# Adafruit_Voice_Bonnet.net
KiCad netlist of a schematic drawn in EAGLE
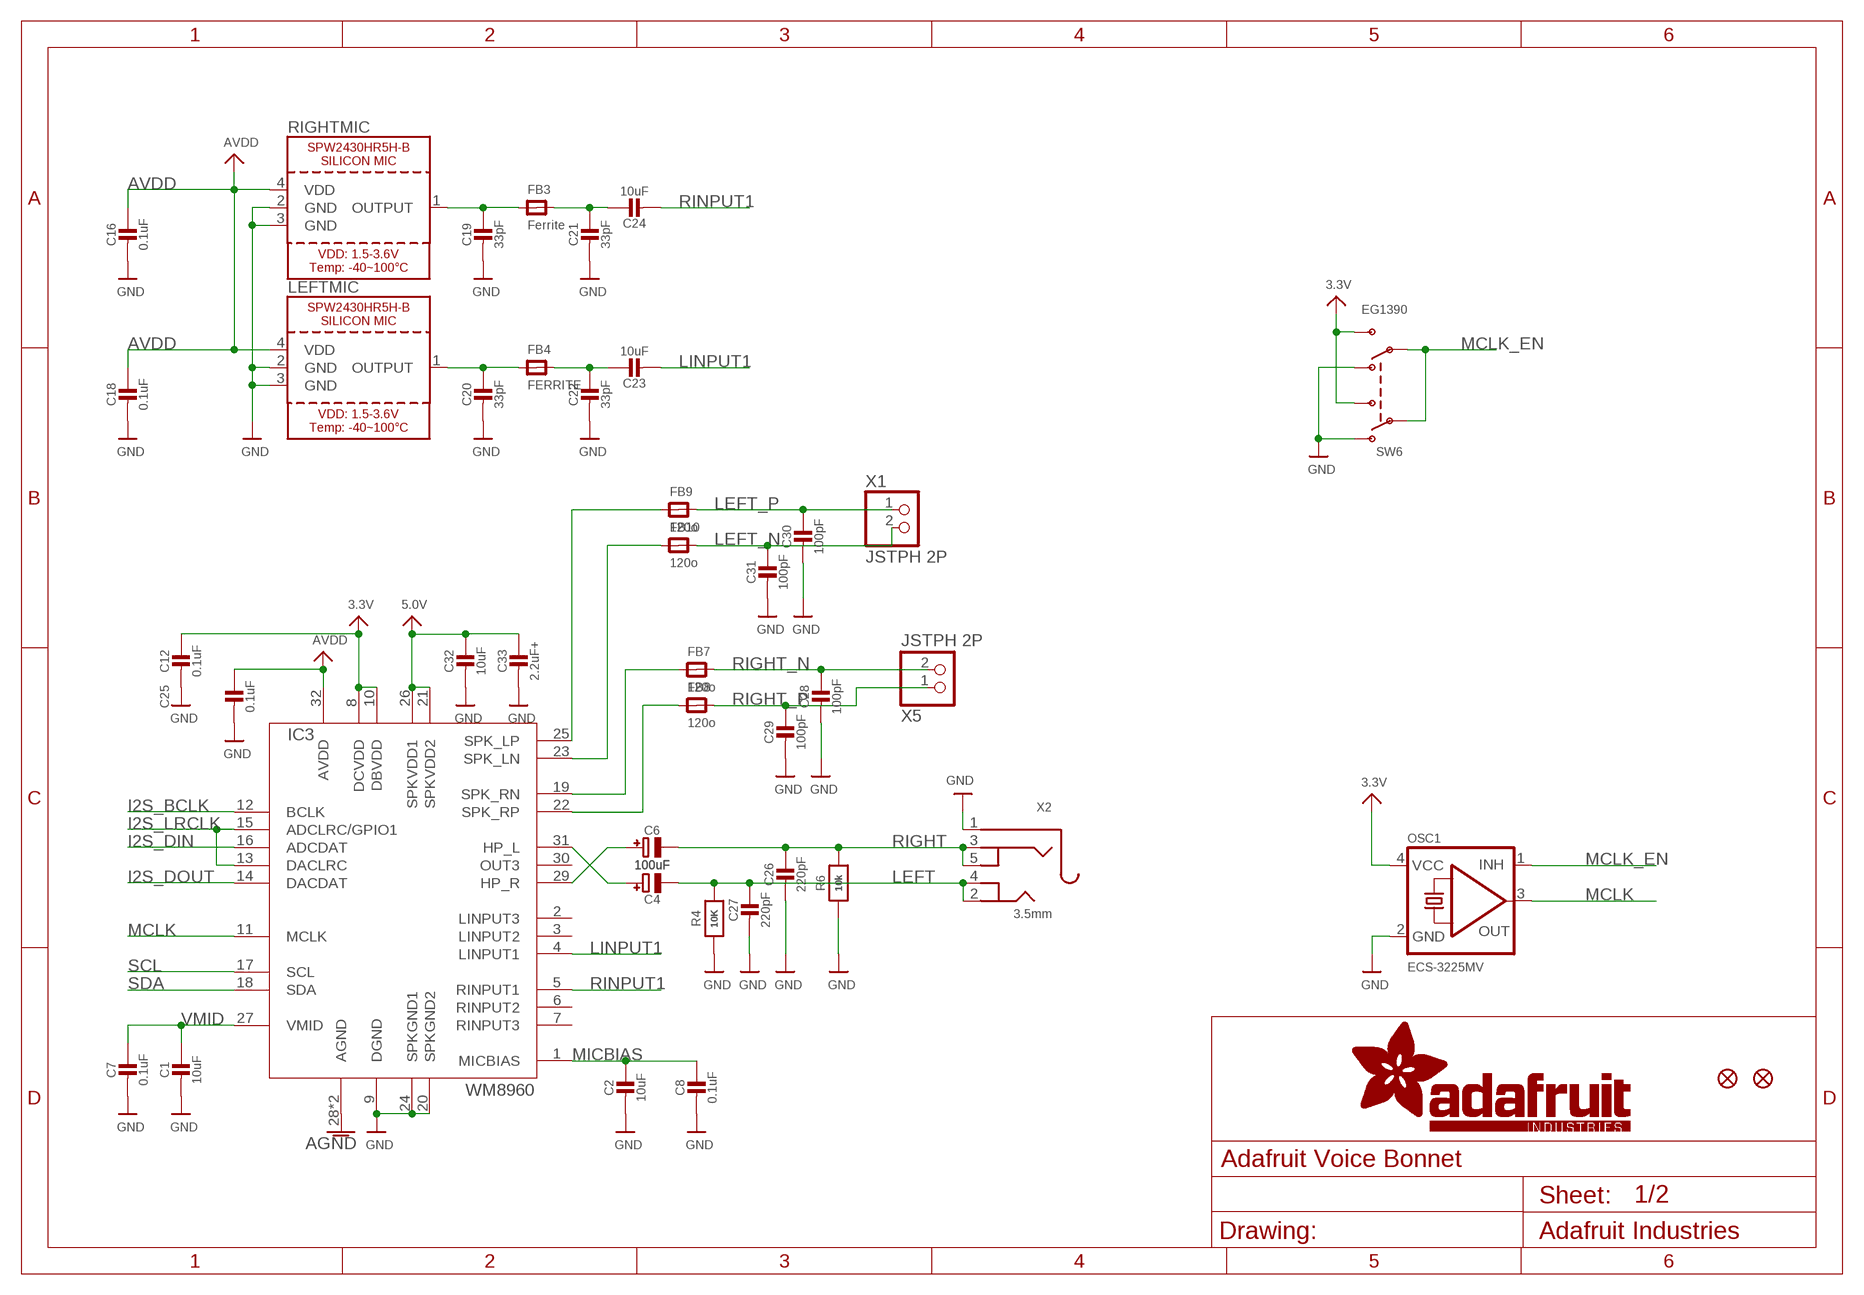
[diagram p0: schematic, sheet 1]
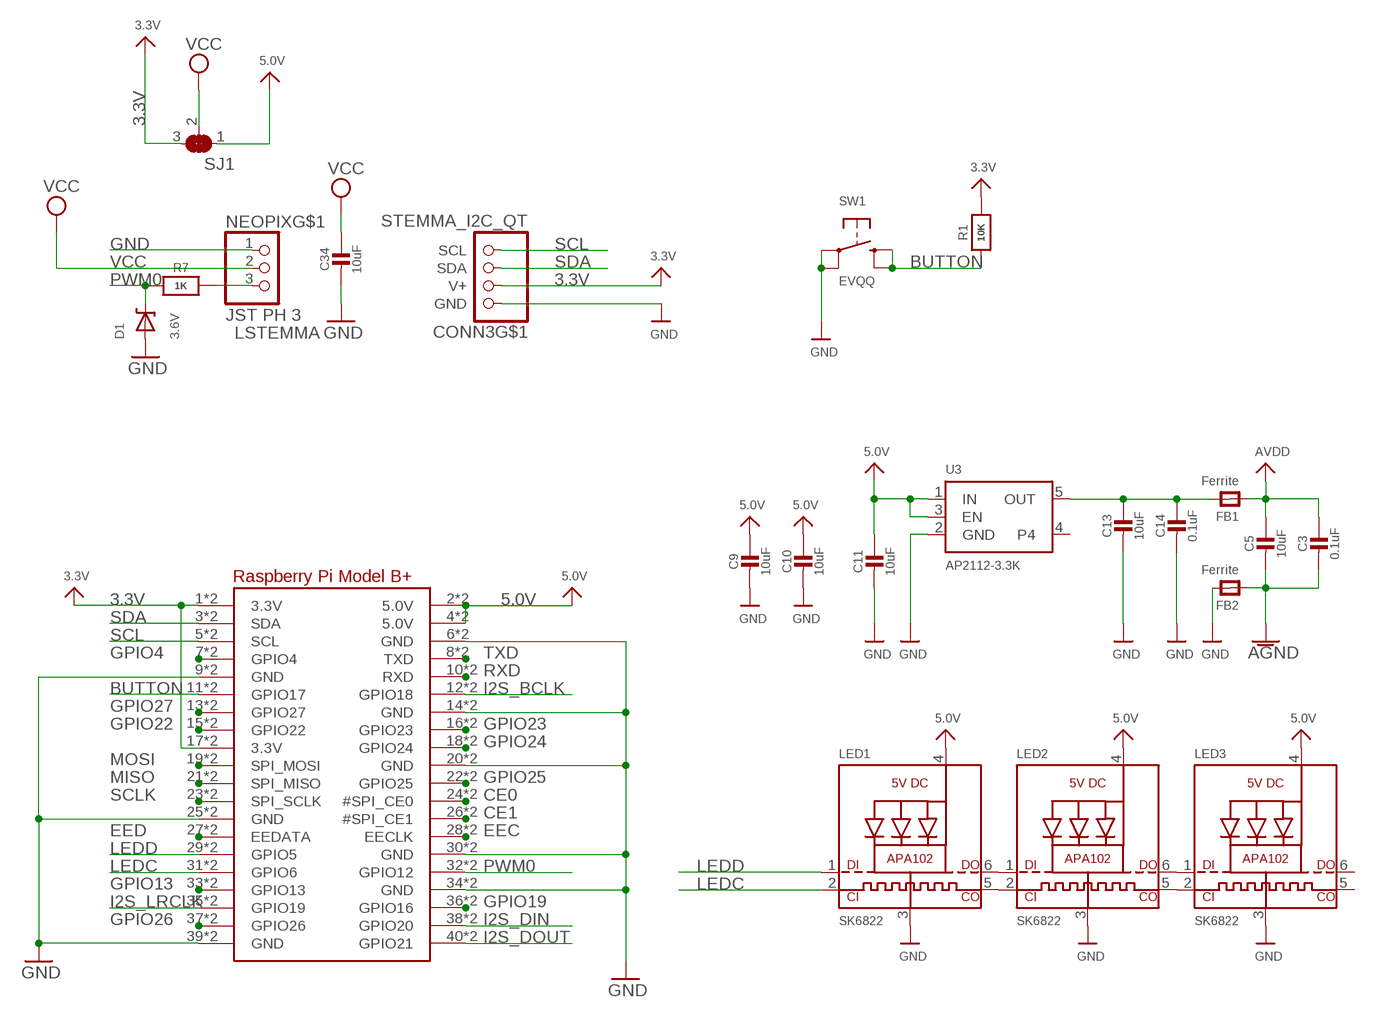
[diagram p1: schematic, sheet 2]

(export (version "E")
  (design (tool "Eeschema 10.0.6"))
  (components
    (comp (ref "C1")
      (value "10uF")
      (footprint "eagle-import:0805-NO")
      (libsource (lib "eagle-import") (part "CAP_CERAMIC0805-NOOUTLINE"))
    )
    (comp (ref "C2")
      (value "10uF")
      (footprint "eagle-import:0805-NO")
      (libsource (lib "eagle-import") (part "CAP_CERAMIC0805-NOOUTLINE"))
    )
    (comp (ref "C4")
      (value "100uF")
      (footprint "eagle-import:PANASONIC_C")
      (libsource (lib "eagle-import") (part "CAP_ELECTROLYTICPANASONIC_C"))
    )
    (comp (ref "C6")
      (value "100uF")
      (footprint "eagle-import:PANASONIC_C")
      (libsource (lib "eagle-import") (part "CAP_ELECTROLYTICPANASONIC_C"))
    )
    (comp (ref "C7")
      (value "0.1uF")
      (footprint "eagle-import:0603-NO")
      (libsource (lib "eagle-import") (part "CAP_CERAMIC0603_NO"))
    )
    (comp (ref "C8")
      (value "0.1uF")
      (footprint "eagle-import:0603-NO")
      (libsource (lib "eagle-import") (part "CAP_CERAMIC0603_NO"))
    )
    (comp (ref "C12")
      (value "0.1uF")
      (footprint "eagle-import:0603-NO")
      (libsource (lib "eagle-import") (part "CAP_CERAMIC0603_NO"))
    )
    (comp (ref "C16")
      (value "0.1uF")
      (footprint "eagle-import:0603-NO")
      (libsource (lib "eagle-import") (part "CAP_CERAMIC0603_NO"))
    )
    (comp (ref "C18")
      (value "0.1uF")
      (footprint "eagle-import:0603-NO")
      (libsource (lib "eagle-import") (part "CAP_CERAMIC0603_NO"))
    )
    (comp (ref "C19")
      (value "33pF")
      (footprint "eagle-import:0603-NO")
      (libsource (lib "eagle-import") (part "CAP_CERAMIC0603_NO"))
    )
    (comp (ref "C20")
      (value "33pF")
      (footprint "eagle-import:0603-NO")
      (libsource (lib "eagle-import") (part "CAP_CERAMIC0603_NO"))
    )
    (comp (ref "C21")
      (value "33pF")
      (footprint "eagle-import:0603-NO")
      (libsource (lib "eagle-import") (part "CAP_CERAMIC0603_NO"))
    )
    (comp (ref "C22")
      (value "33pF")
      (footprint "eagle-import:0603-NO")
      (libsource (lib "eagle-import") (part "CAP_CERAMIC0603_NO"))
    )
    (comp (ref "C23")
      (value "10uF")
      (footprint "eagle-import:0805-NO")
      (libsource (lib "eagle-import") (part "CAP_CERAMIC0805-NOOUTLINE"))
    )
    (comp (ref "C24")
      (value "10uF")
      (footprint "eagle-import:0805-NO")
      (libsource (lib "eagle-import") (part "CAP_CERAMIC0805-NOOUTLINE"))
    )
    (comp (ref "C25")
      (value "0.1uF")
      (footprint "eagle-import:0603-NO")
      (libsource (lib "eagle-import") (part "CAP_CERAMIC0603_NO"))
    )
    (comp (ref "C26")
      (value "220pF")
      (footprint "eagle-import:0603-NO")
      (libsource (lib "eagle-import") (part "CAP_CERAMIC0603_NO"))
    )
    (comp (ref "C27")
      (value "220pF")
      (footprint "eagle-import:0603-NO")
      (libsource (lib "eagle-import") (part "CAP_CERAMIC0603_NO"))
    )
    (comp (ref "C28")
      (value "100pF")
      (footprint "eagle-import:0603-NO")
      (libsource (lib "eagle-import") (part "CAP_CERAMIC0603_NO"))
    )
    (comp (ref "C29")
      (value "100pF")
      (footprint "eagle-import:0603-NO")
      (libsource (lib "eagle-import") (part "CAP_CERAMIC0603_NO"))
    )
    (comp (ref "C30")
      (value "100pF")
      (footprint "eagle-import:0603-NO")
      (libsource (lib "eagle-import") (part "CAP_CERAMIC0603_NO"))
    )
    (comp (ref "C31")
      (value "100pF")
      (footprint "eagle-import:0603-NO")
      (libsource (lib "eagle-import") (part "CAP_CERAMIC0603_NO"))
    )
    (comp (ref "C32")
      (value "10uF")
      (footprint "eagle-import:0805-NO")
      (libsource (lib "eagle-import") (part "CAP_CERAMIC0805-NOOUTLINE"))
    )
    (comp (ref "C33")
      (value "2.2uF+")
      (footprint "eagle-import:0805-NO")
      (libsource (lib "eagle-import") (part "CAP_CERAMIC0805-NOOUTLINE"))
    )
    (comp (ref "FB3")
      (value "Ferrite")
      (footprint "eagle-import:0805-NO")
      (libsource (lib "eagle-import") (part "FERRITE-0805NO"))
    )
    (comp (ref "FB4")
      (value "FERRITE")
      (footprint "eagle-import:0805-NO")
      (libsource (lib "eagle-import") (part "FERRITE-0805NO"))
    )
    (comp (ref "FB7")
      (value "120o")
      (footprint "eagle-import:0805-NO")
      (libsource (lib "eagle-import") (part "FERRITE-0805NO"))
    )
    (comp (ref "FB8")
      (value "120o")
      (footprint "eagle-import:0805-NO")
      (libsource (lib "eagle-import") (part "FERRITE-0805NO"))
    )
    (comp (ref "FB9")
      (value "120o")
      (footprint "eagle-import:0805-NO")
      (libsource (lib "eagle-import") (part "FERRITE-0805NO"))
    )
    (comp (ref "FB10")
      (value "120o")
      (footprint "eagle-import:0805-NO")
      (libsource (lib "eagle-import") (part "FERRITE-0805NO"))
    )
    (comp (ref "FID1")
      (value "FIDUCIAL_1MM")
      (footprint "eagle-import:FIDUCIAL_1MM")
      (libsource (lib "eagle-import") (part "FIDUCIAL_1MM"))
    )
    (comp (ref "FID2")
      (value "FIDUCIAL_1MM")
      (footprint "eagle-import:FIDUCIAL_1MM")
      (libsource (lib "eagle-import") (part "FIDUCIAL_1MM"))
    )
    (comp (ref "IC3")
      (value "WM8960")
      (footprint "eagle-import:QFN32_5MM")
      (libsource (lib "eagle-import") (part "WM8960"))
    )
    (comp (ref "LEFTMIC")
      (value "SPW2430HR5H-B")
      (footprint "eagle-import:SPW2430HR5H-B")
      (libsource (lib "eagle-import") (part "SPW2430HR5H-B"))
    )
    (comp (ref "OSC1")
      (value "ECS-3225MV")
      (footprint "eagle-import:OSC_3.2X2.5MM")
      (libsource (lib "eagle-import") (part "OSCILLATOR3.2X2.5"))
    )
    (comp (ref "R4")
      (value "10K")
      (footprint "eagle-import:0603-NO")
      (libsource (lib "eagle-import") (part "RESISTOR_0603_NOOUT"))
    )
    (comp (ref "R6")
      (value "10k")
      (footprint "eagle-import:0603-NO")
      (libsource (lib "eagle-import") (part "RESISTOR_0603_NOOUT"))
    )
    (comp (ref "RIGHTMIC")
      (value "SPW2430HR5H-B")
      (footprint "eagle-import:SPW2430HR5H-B")
      (libsource (lib "eagle-import") (part "SPW2430HR5H-B"))
    )
    (comp (ref "SW6")
      (value "EG1390")
      (footprint "eagle-import:EG1390")
      (libsource (lib "eagle-import") (part "SWITCH_DPDTEG1390"))
    )
    (comp (ref "X1")
      (value "JSTPH 2P")
      (footprint "eagle-import:JSTPH2")
      (libsource (lib "eagle-import") (part "CON_JST_PH_2PIN"))
    )
    (comp (ref "X2")
      (value "3.5mm")
      (footprint "eagle-import:4UCONN_19269")
      (libsource (lib "eagle-import") (part "AUDIO_3.5MMJACK"))
    )
    (comp (ref "X5")
      (value "JSTPH 2P")
      (footprint "eagle-import:JSTPH2")
      (libsource (lib "eagle-import") (part "CON_JST_PH_2PIN"))
    )
    (comp (ref "C3")
      (value "0.1uF")
      (footprint "eagle-import:0603-NO")
      (libsource (lib "eagle-import") (part "CAP_CERAMIC0603_NO"))
    )
    (comp (ref "C5")
      (value "10uF")
      (footprint "eagle-import:0805-NO")
      (libsource (lib "eagle-import") (part "CAP_CERAMIC0805-NOOUTLINE"))
    )
    (comp (ref "C9")
      (value "10uF")
      (footprint "eagle-import:0805-NO")
      (libsource (lib "eagle-import") (part "CAP_CERAMIC0805-NOOUTLINE"))
    )
    (comp (ref "C10")
      (value "10uF")
      (footprint "eagle-import:0805-NO")
      (libsource (lib "eagle-import") (part "CAP_CERAMIC0805-NOOUTLINE"))
    )
    (comp (ref "C11")
      (value "10uF")
      (footprint "eagle-import:0805-NO")
      (libsource (lib "eagle-import") (part "CAP_CERAMIC0805-NOOUTLINE"))
    )
    (comp (ref "C13")
      (value "10uF")
      (footprint "eagle-import:0805-NO")
      (libsource (lib "eagle-import") (part "CAP_CERAMIC0805-NOOUTLINE"))
    )
    (comp (ref "C14")
      (value "0.1uF")
      (footprint "eagle-import:0603-NO")
      (libsource (lib "eagle-import") (part "CAP_CERAMIC0603_NO"))
    )
    (comp (ref "C34")
      (value "10uF")
      (footprint "eagle-import:0805-NO")
      (libsource (lib "eagle-import") (part "CAP_CERAMIC0805-NOOUTLINE"))
    )
    (comp (ref "CONN3")
      (value "STEMMA_I2C_QT")
      (footprint "eagle-import:JST_SH4")
      (libsource (lib "eagle-import") (part "STEMMA_I2C_QT"))
    )
    (comp (ref "D1")
      (value "3.6V")
      (footprint "eagle-import:SOD-323")
      (libsource (lib "eagle-import") (part "DIODE-ZENERSOD323"))
    )
    (comp (ref "FB1")
      (value "Ferrite")
      (footprint "eagle-import:0805")
      (libsource (lib "eagle-import") (part "FERRITE0805"))
    )
    (comp (ref "FB2")
      (value "Ferrite")
      (footprint "eagle-import:0805")
      (libsource (lib "eagle-import") (part "FERRITE0805"))
    )
    (comp (ref "LED1")
      (value "SK6822")
      (footprint "eagle-import:APA102")
      (libsource (lib "eagle-import") (part "APA102"))
    )
    (comp (ref "LED2")
      (value "SK6822")
      (footprint "eagle-import:APA102")
      (libsource (lib "eagle-import") (part "APA102"))
    )
    (comp (ref "LED3")
      (value "SK6822")
      (footprint "eagle-import:APA102")
      (libsource (lib "eagle-import") (part "APA102"))
    )
    (comp (ref "NEOPIX")
      (value "JST PH 3")
      (footprint "eagle-import:JSTPH3")
      (libsource (lib "eagle-import") (part "CON_JST_PH_3PIN"))
    )
    (comp (ref "R1")
      (value "10K")
      (footprint "eagle-import:0603-NO")
      (libsource (lib "eagle-import") (part "RESISTOR_0603_NOOUT"))
    )
    (comp (ref "R7")
      (value "1K")
      (footprint "eagle-import:0603-NO")
      (libsource (lib "eagle-import") (part "RESISTOR_0603_NOOUT"))
    )
    (comp (ref "RPI1")
      (value "RASPBERRYPI_BPLUS_BONNET_THMSMT")
      (footprint "eagle-import:PI_BONNET_THMSMT")
      (libsource (lib "eagle-import") (part "RASPBERRYPI_BPLUS_BONNET_THMSMT"))
    )
    (comp (ref "SJ1")
      (value "SOLDERJUMPER_2WAY")
      (footprint "eagle-import:SOLDERJUMPER_2WAY_OPEN_NOPASTE")
      (libsource (lib "eagle-import") (part "SOLDERJUMPER_2WAY"))
    )
    (comp (ref "SW1")
      (value "EVQQ")
      (footprint "eagle-import:EVQ-Q2_SMALLER")
      (libsource (lib "eagle-import") (part "SWITCH_TACT_SMT_EVQQ2_SMALL"))
    )
    (comp (ref "U3")
      (value "AP2112-3.3K")
      (footprint "eagle-import:SOT23-5")
      (libsource (lib "eagle-import") (part "VREG_SOT23-5"))
    )
  )
  (nets
    (net (code "1") (name "3.3V") (class "Default")
      (node (ref "C12") (pin "1") (pinfunction "1_1") (pintype "passive"))
      (node (ref "CONN3") (pin "2") (pinfunction "V+_2") (pintype "passive"))
      (node (ref "IC3") (pin "10") (pinfunction "DBVDD_10") (pintype "power_in"))
      (node (ref "IC3") (pin "8") (pinfunction "DCVDD_8") (pintype "power_in"))
      (node (ref "OSC1") (pin "4") (pinfunction "VCC_4") (pintype "power_in"))
      (node (ref "R1") (pin "2") (pinfunction "2_2") (pintype "passive"))
      (node (ref "RPI1") (pin "1") (pinfunction "3.3V_1") (pintype "power_in"))
      (node (ref "RPI1") (pin "17") (pinfunction "3.3V_17") (pintype "power_in"))
      (node (ref "RPI1") (pin "S1") (pinfunction "3.3V_S1") (pintype "power_in"))
      (node (ref "RPI1") (pin "S17") (pinfunction "3.3V_S17") (pintype "power_in"))
      (node (ref "SJ1") (pin "3") (pinfunction "3_3") (pintype "passive"))
      (node (ref "SW6") (pin "S1") (pinfunction "S1_S1") (pintype "passive"))
      (node (ref "SW6") (pin "S2") (pinfunction "S2_S2") (pintype "passive"))
    )
    (net (code "2") (name "5.0V") (class "Default")
      (node (ref "C10") (pin "1") (pinfunction "1_1") (pintype "passive"))
      (node (ref "C11") (pin "1") (pinfunction "1_1") (pintype "passive"))
      (node (ref "C32") (pin "1") (pinfunction "1_1") (pintype "passive"))
      (node (ref "C33") (pin "1") (pinfunction "1_1") (pintype "passive"))
      (node (ref "C9") (pin "1") (pinfunction "1_1") (pintype "passive"))
      (node (ref "IC3") (pin "21") (pinfunction "SPKVDD2_21") (pintype "power_in"))
      (node (ref "IC3") (pin "26") (pinfunction "SPKVDD1_26") (pintype "power_in"))
      (node (ref "LED1") (pin "4") (pinfunction "VDD_4") (pintype "power_in"))
      (node (ref "LED2") (pin "4") (pinfunction "VDD_4") (pintype "power_in"))
      (node (ref "LED3") (pin "4") (pinfunction "VDD_4") (pintype "power_in"))
      (node (ref "RPI1") (pin "2") (pinfunction "5.0V_2") (pintype "power_in"))
      (node (ref "RPI1") (pin "4") (pinfunction "5.0V_4") (pintype "power_in"))
      (node (ref "RPI1") (pin "S2") (pinfunction "5.0V_S2") (pintype "power_in"))
      (node (ref "RPI1") (pin "S4") (pinfunction "5.0V_S4") (pintype "power_in"))
      (node (ref "SJ1") (pin "1") (pinfunction "1_1") (pintype "passive"))
      (node (ref "U3") (pin "1") (pinfunction "IN_1") (pintype "power_in"))
      (node (ref "U3") (pin "3") (pinfunction "EN_3") (pintype "input"))
    )
    (net (code "3") (name "AGND") (class "Default")
      (node (ref "C3") (pin "2") (pinfunction "2_2") (pintype "passive"))
      (node (ref "C5") (pin "2") (pinfunction "2_2") (pintype "passive"))
      (node (ref "FB2") (pin "1") (pinfunction "P$1_1") (pintype "passive"))
      (node (ref "IC3") (pin "28") (pinfunction "AGND_28") (pintype "power_in"))
      (node (ref "IC3") (pin "33") (pinfunction "AGND_33") (pintype "power_in"))
    )
    (net (code "4") (name "AVDD") (class "Default")
      (node (ref "C16") (pin "1") (pinfunction "1_1") (pintype "passive"))
      (node (ref "C18") (pin "1") (pinfunction "1_1") (pintype "passive"))
      (node (ref "C25") (pin "1") (pinfunction "1_1") (pintype "passive"))
      (node (ref "C3") (pin "1") (pinfunction "1_1") (pintype "passive"))
      (node (ref "C5") (pin "1") (pinfunction "1_1") (pintype "passive"))
      (node (ref "FB1") (pin "1") (pinfunction "P$1_1") (pintype "passive"))
      (node (ref "IC3") (pin "32") (pinfunction "AVDD_32") (pintype "power_in"))
      (node (ref "LEFTMIC") (pin "4") (pinfunction "VDD_4") (pintype "power_in"))
      (node (ref "RIGHTMIC") (pin "4") (pinfunction "VDD_4") (pintype "power_in"))
    )
    (net (code "5") (name "BUTTON") (class "Default")
      (node (ref "R1") (pin "1") (pinfunction "1_1") (pintype "passive"))
      (node (ref "RPI1") (pin "11") (pinfunction "GPIO17_11") (pintype "bidirectional"))
      (node (ref "RPI1") (pin "S11") (pinfunction "GPIO17_S11") (pintype "bidirectional"))
      (node (ref "SW1") (pin "B") (pinfunction "S_B") (pintype "passive"))
      (node (ref "SW1") (pin "B'") (pinfunction "S1_B'") (pintype "passive"))
    )
    (net (code "10") (name "CE0") (class "Default")
      (node (ref "RPI1") (pin "24") (pinfunction "#SPI_CE0_24") (pintype "bidirectional"))
      (node (ref "RPI1") (pin "S24") (pinfunction "#SPI_CE0_S24") (pintype "bidirectional"))
    )
    (net (code "20") (name "CE1") (class "Default")
      (node (ref "RPI1") (pin "26") (pinfunction "#SPI_CE1_26") (pintype "bidirectional"))
      (node (ref "RPI1") (pin "S26") (pinfunction "#SPI_CE1_S26") (pintype "bidirectional"))
    )
    (net (code "21") (name "EEC") (class "Default")
      (node (ref "RPI1") (pin "28") (pinfunction "EECLK_28") (pintype "bidirectional"))
      (node (ref "RPI1") (pin "S28") (pinfunction "EECLK_S28") (pintype "bidirectional"))
    )
    (net (code "22") (name "EED") (class "Default")
      (node (ref "RPI1") (pin "27") (pinfunction "EEDATA_27") (pintype "bidirectional"))
      (node (ref "RPI1") (pin "S27") (pinfunction "EEDATA_S27") (pintype "bidirectional"))
    )
    (net (code "23") (name "GND") (class "Default")
      (node (ref "C1") (pin "2") (pinfunction "2_2") (pintype "passive"))
      (node (ref "C10") (pin "2") (pinfunction "2_2") (pintype "passive"))
      (node (ref "C11") (pin "2") (pinfunction "2_2") (pintype "passive"))
      (node (ref "C12") (pin "2") (pinfunction "2_2") (pintype "passive"))
      (node (ref "C13") (pin "2") (pinfunction "2_2") (pintype "passive"))
      (node (ref "C14") (pin "2") (pinfunction "2_2") (pintype "passive"))
      (node (ref "C16") (pin "2") (pinfunction "2_2") (pintype "passive"))
      (node (ref "C18") (pin "2") (pinfunction "2_2") (pintype "passive"))
      (node (ref "C19") (pin "2") (pinfunction "2_2") (pintype "passive"))
      (node (ref "C2") (pin "2") (pinfunction "2_2") (pintype "passive"))
      (node (ref "C20") (pin "2") (pinfunction "2_2") (pintype "passive"))
      (node (ref "C21") (pin "2") (pinfunction "2_2") (pintype "passive"))
      (node (ref "C22") (pin "2") (pinfunction "2_2") (pintype "passive"))
      (node (ref "C25") (pin "2") (pinfunction "2_2") (pintype "passive"))
      (node (ref "C26") (pin "2") (pinfunction "2_2") (pintype "passive"))
      (node (ref "C27") (pin "2") (pinfunction "2_2") (pintype "passive"))
      (node (ref "C28") (pin "2") (pinfunction "2_2") (pintype "passive"))
      (node (ref "C29") (pin "2") (pinfunction "2_2") (pintype "passive"))
      (node (ref "C30") (pin "2") (pinfunction "2_2") (pintype "passive"))
      (node (ref "C31") (pin "2") (pinfunction "2_2") (pintype "passive"))
      (node (ref "C32") (pin "2") (pinfunction "2_2") (pintype "passive"))
      (node (ref "C33") (pin "2") (pinfunction "2_2") (pintype "passive"))
      (node (ref "C34") (pin "2") (pinfunction "2_2") (pintype "passive"))
      (node (ref "C7") (pin "2") (pinfunction "2_2") (pintype "passive"))
      (node (ref "C8") (pin "2") (pinfunction "2_2") (pintype "passive"))
      (node (ref "C9") (pin "2") (pinfunction "2_2") (pintype "passive"))
      (node (ref "CONN3") (pin "1") (pinfunction "GND_1") (pintype "passive"))
      (node (ref "D1") (pin "A") (pinfunction "A_A") (pintype "passive"))
      (node (ref "FB2") (pin "2") (pinfunction "P$2_2") (pintype "passive"))
      (node (ref "IC3") (pin "20") (pinfunction "SPKGND2_20") (pintype "power_in"))
      (node (ref "IC3") (pin "24") (pinfunction "SPKGND1_24") (pintype "power_in"))
      (node (ref "IC3") (pin "9") (pinfunction "DGND_9") (pintype "power_in"))
      (node (ref "LED1") (pin "3") (pinfunction "GND_3") (pintype "power_in"))
      (node (ref "LED2") (pin "3") (pinfunction "GND_3") (pintype "power_in"))
      (node (ref "LED3") (pin "3") (pinfunction "GND_3") (pintype "power_in"))
      (node (ref "LEFTMIC") (pin "2") (pinfunction "GND_2") (pintype "power_in"))
      (node (ref "LEFTMIC") (pin "3") (pinfunction "GND_3") (pintype "power_in"))
      (node (ref "NEOPIX") (pin "1") (pinfunction "1_1") (pintype "passive"))
      (node (ref "OSC1") (pin "2") (pinfunction "GND_2") (pintype "power_in"))
      (node (ref "R4") (pin "1") (pinfunction "1_1") (pintype "passive"))
      (node (ref "R6") (pin "1") (pinfunction "1_1") (pintype "passive"))
      (node (ref "RIGHTMIC") (pin "2") (pinfunction "GND_2") (pintype "power_in"))
      (node (ref "RIGHTMIC") (pin "3") (pinfunction "GND_3") (pintype "power_in"))
      (node (ref "RPI1") (pin "14") (pinfunction "GND_14") (pintype "power_in"))
      (node (ref "RPI1") (pin "20") (pinfunction "GND_20") (pintype "power_in"))
      (node (ref "RPI1") (pin "25") (pinfunction "GND_25") (pintype "power_in"))
      (node (ref "RPI1") (pin "30") (pinfunction "GND_30") (pintype "power_in"))
      (node (ref "RPI1") (pin "34") (pinfunction "GND_34") (pintype "power_in"))
      (node (ref "RPI1") (pin "39") (pinfunction "GND_39") (pintype "power_in"))
      (node (ref "RPI1") (pin "6") (pinfunction "GND_6") (pintype "power_in"))
      (node (ref "RPI1") (pin "9") (pinfunction "GND_9") (pintype "power_in"))
      (node (ref "RPI1") (pin "S14") (pinfunction "GND_S14") (pintype "power_in"))
      (node (ref "RPI1") (pin "S20") (pinfunction "GND_S20") (pintype "power_in"))
      (node (ref "RPI1") (pin "S25") (pinfunction "GND_S25") (pintype "power_in"))
      (node (ref "RPI1") (pin "S30") (pinfunction "GND_S30") (pintype "power_in"))
      (node (ref "RPI1") (pin "S34") (pinfunction "GND_S34") (pintype "power_in"))
      (node (ref "RPI1") (pin "S39") (pinfunction "GND_S39") (pintype "power_in"))
      (node (ref "RPI1") (pin "S6") (pinfunction "GND_S6") (pintype "power_in"))
      (node (ref "RPI1") (pin "S9") (pinfunction "GND_S9") (pintype "power_in"))
      (node (ref "SW1") (pin "A") (pinfunction "P_A") (pintype "passive"))
      (node (ref "SW1") (pin "A'") (pinfunction "P1_A'") (pintype "passive"))
      (node (ref "SW6") (pin "O1") (pinfunction "O1_O1") (pintype "passive"))
      (node (ref "SW6") (pin "O2") (pinfunction "O2_O2") (pintype "passive"))
      (node (ref "U3") (pin "2") (pinfunction "GND_2") (pintype "power_in"))
      (node (ref "X2") (pin "1") (pinfunction "P$1_1") (pintype "bidirectional"))
    )
    (net (code "24") (name "GPIO4") (class "Default")
      (node (ref "RPI1") (pin "7") (pinfunction "GPIO4_7") (pintype "bidirectional"))
      (node (ref "RPI1") (pin "S7") (pinfunction "GPIO4_S7") (pintype "bidirectional"))
    )
    (net (code "25") (name "GPIO13") (class "Default")
      (node (ref "RPI1") (pin "33") (pinfunction "GPIO13_33") (pintype "bidirectional"))
      (node (ref "RPI1") (pin "S33") (pinfunction "GPIO13_S33") (pintype "bidirectional"))
    )
    (net (code "26") (name "GPIO19") (class "Default")
      (node (ref "RPI1") (pin "36") (pinfunction "GPIO16_36") (pintype "bidirectional"))
      (node (ref "RPI1") (pin "S36") (pinfunction "GPIO16_S36") (pintype "bidirectional"))
    )
    (net (code "27") (name "GPIO22") (class "Default")
      (node (ref "RPI1") (pin "15") (pinfunction "GPIO22_15") (pintype "bidirectional"))
      (node (ref "RPI1") (pin "S15") (pinfunction "GPIO22_S15") (pintype "bidirectional"))
    )
    (net (code "28") (name "GPIO23") (class "Default")
      (node (ref "RPI1") (pin "16") (pinfunction "GPIO23_16") (pintype "bidirectional"))
      (node (ref "RPI1") (pin "S16") (pinfunction "GPIO23_S16") (pintype "bidirectional"))
    )
    (net (code "29") (name "GPIO24") (class "Default")
      (node (ref "RPI1") (pin "18") (pinfunction "GPIO24_18") (pintype "bidirectional"))
      (node (ref "RPI1") (pin "S18") (pinfunction "GPIO24_S18") (pintype "bidirectional"))
    )
    (net (code "30") (name "GPIO25") (class "Default")
      (node (ref "RPI1") (pin "22") (pinfunction "GPIO25_22") (pintype "bidirectional"))
      (node (ref "RPI1") (pin "S22") (pinfunction "GPIO25_S22") (pintype "bidirectional"))
    )
    (net (code "31") (name "GPIO26") (class "Default")
      (node (ref "RPI1") (pin "37") (pinfunction "GPIO26_37") (pintype "bidirectional"))
      (node (ref "RPI1") (pin "S37") (pinfunction "GPIO26_S37") (pintype "bidirectional"))
    )
    (net (code "32") (name "GPIO27") (class "Default")
      (node (ref "RPI1") (pin "13") (pinfunction "GPIO27_13") (pintype "bidirectional"))
      (node (ref "RPI1") (pin "S13") (pinfunction "GPIO27_S13") (pintype "bidirectional"))
    )
    (net (code "33") (name "I2S_BCLK") (class "Default")
      (node (ref "IC3") (pin "12") (pinfunction "BCLK_12") (pintype "bidirectional"))
      (node (ref "RPI1") (pin "12") (pinfunction "GPIO18_12") (pintype "bidirectional"))
      (node (ref "RPI1") (pin "S12") (pinfunction "GPIO18_S12") (pintype "bidirectional"))
    )
    (net (code "36") (name "I2S_DIN") (class "Default")
      (node (ref "IC3") (pin "16") (pinfunction "ADCDAT_16") (pintype "input"))
      (node (ref "RPI1") (pin "38") (pinfunction "GPIO20_38") (pintype "bidirectional"))
      (node (ref "RPI1") (pin "S38") (pinfunction "GPIO20_S38") (pintype "bidirectional"))
    )
    (net (code "37") (name "I2S_DOUT") (class "Default")
      (node (ref "IC3") (pin "14") (pinfunction "DACDAT_14") (pintype "bidirectional"))
      (node (ref "RPI1") (pin "40") (pinfunction "GPIO21_40") (pintype "bidirectional"))
      (node (ref "RPI1") (pin "S40") (pinfunction "GPIO21_S40") (pintype "bidirectional"))
    )
    (net (code "38") (name "I2S_LRCLK") (class "Default")
      (node (ref "IC3") (pin "13") (pinfunction "DACLRC_13") (pintype "bidirectional"))
      (node (ref "IC3") (pin "15") (pinfunction "ADCLRC/GPIO1_15") (pintype "bidirectional"))
      (node (ref "RPI1") (pin "35") (pinfunction "GPIO19_35") (pintype "bidirectional"))
      (node (ref "RPI1") (pin "S35") (pinfunction "GPIO19_S35") (pintype "bidirectional"))
    )
    (net (code "39") (name "LEDC") (class "Default")
      (node (ref "LED1") (pin "2") (pinfunction "CKI_2") (pintype "input"))
      (node (ref "RPI1") (pin "31") (pinfunction "GPIO6_31") (pintype "bidirectional"))
      (node (ref "RPI1") (pin "S31") (pinfunction "GPIO6_S31") (pintype "bidirectional"))
    )
    (net (code "40") (name "LEDD") (class "Default")
      (node (ref "LED1") (pin "1") (pinfunction "DI_1") (pintype "input"))
      (node (ref "RPI1") (pin "29") (pinfunction "GPIO5_29") (pintype "bidirectional"))
      (node (ref "RPI1") (pin "S29") (pinfunction "GPIO5_S29") (pintype "bidirectional"))
    )
    (net (code "41") (name "LEFT") (class "Default")
      (node (ref "C27") (pin "1") (pinfunction "1_1") (pintype "passive"))
      (node (ref "C4") (pin "-") (pinfunction "-_-") (pintype "passive"))
      (node (ref "R4") (pin "2") (pinfunction "2_2") (pintype "passive"))
      (node (ref "X2") (pin "2") (pinfunction "P$5_2") (pintype "bidirectional"))
      (node (ref "X2") (pin "4") (pinfunction "P$4_4") (pintype "bidirectional"))
    )
    (net (code "42") (name "LEFT_N") (class "Default")
      (node (ref "C31") (pin "1") (pinfunction "1_1") (pintype "passive"))
      (node (ref "FB10") (pin "2") (pinfunction "P$2_2") (pintype "passive"))
      (node (ref "X1") (pin "2") (pinfunction "2_2") (pintype "passive"))
    )
    (net (code "43") (name "LEFT_P") (class "Default")
      (node (ref "C30") (pin "1") (pinfunction "1_1") (pintype "passive"))
      (node (ref "FB9") (pin "2") (pinfunction "P$2_2") (pintype "passive"))
      (node (ref "X1") (pin "1") (pinfunction "1_1") (pintype "passive"))
    )
    (net (code "44") (name "LINPUT1") (class "Default")
      (node (ref "C23") (pin "2") (pinfunction "2_2") (pintype "passive"))
      (node (ref "IC3") (pin "4") (pinfunction "LINPUT1_4") (pintype "input"))
    )
    (net (code "45") (name "LSTEMMA") (class "Default")
      (node (ref "NEOPIX") (pin "3") (pinfunction "3_3") (pintype "passive"))
      (node (ref "R7") (pin "1") (pinfunction "1_1") (pintype "passive"))
    )
    (net (code "46") (name "MCLK") (class "Default")
      (node (ref "IC3") (pin "11") (pinfunction "MCLK_11") (pintype "input"))
      (node (ref "OSC1") (pin "3") (pinfunction "OUT_3") (pintype "output"))
    )
    (net (code "47") (name "MCLK_EN") (class "Default")
      (node (ref "OSC1") (pin "1") (pinfunction "INH_1") (pintype "bidirectional"))
      (node (ref "SW6") (pin "P1") (pinfunction "P1_P1") (pintype "passive"))
      (node (ref "SW6") (pin "P2") (pinfunction "P2_P2") (pintype "passive"))
    )
    (net (code "48") (name "MICBIAS") (class "Default")
      (node (ref "C2") (pin "1") (pinfunction "1_1") (pintype "passive"))
      (node (ref "C8") (pin "1") (pinfunction "1_1") (pintype "passive"))
      (node (ref "IC3") (pin "1") (pinfunction "MICBIAS_1") (pintype "output"))
    )
    (net (code "49") (name "MISO") (class "Default")
      (node (ref "RPI1") (pin "21") (pinfunction "SPI_MISO_21") (pintype "bidirectional"))
      (node (ref "RPI1") (pin "S21") (pinfunction "SPI_MISO_S21") (pintype "bidirectional"))
    )
    (net (code "50") (name "MOSI") (class "Default")
      (node (ref "RPI1") (pin "19") (pinfunction "SPI_MOSI_19") (pintype "bidirectional"))
      (node (ref "RPI1") (pin "S19") (pinfunction "SPI_MOSI_S19") (pintype "bidirectional"))
    )
    (net (code "51") (name "Net-(FB1-P$2)") (class "Default")
      (node (ref "C13") (pin "1") (pinfunction "1_1") (pintype "passive"))
      (node (ref "C14") (pin "1") (pinfunction "1_1") (pintype "passive"))
      (node (ref "FB1") (pin "2") (pinfunction "P$2_2") (pintype "passive"))
      (node (ref "U3") (pin "5") (pinfunction "OUT_5") (pintype "power_in"))
    )
    (net (code "52") (name "Net-(FB3-P$1)") (class "Default")
      (node (ref "C19") (pin "1") (pinfunction "1_1") (pintype "passive"))
      (node (ref "FB3") (pin "1") (pinfunction "P$1_1") (pintype "passive"))
      (node (ref "RIGHTMIC") (pin "1") (pinfunction "OUTPUT_1") (pintype "output"))
    )
    (net (code "53") (name "Net-(FB3-P$2)") (class "Default")
      (node (ref "C21") (pin "1") (pinfunction "1_1") (pintype "passive"))
      (node (ref "C24") (pin "1") (pinfunction "1_1") (pintype "passive"))
      (node (ref "FB3") (pin "2") (pinfunction "P$2_2") (pintype "passive"))
    )
    (net (code "54") (name "Net-(FB4-P$1)") (class "Default")
      (node (ref "C20") (pin "1") (pinfunction "1_1") (pintype "passive"))
      (node (ref "FB4") (pin "1") (pinfunction "P$1_1") (pintype "passive"))
      (node (ref "LEFTMIC") (pin "1") (pinfunction "OUTPUT_1") (pintype "output"))
    )
    (net (code "55") (name "Net-(FB4-P$2)") (class "Default")
      (node (ref "C22") (pin "1") (pinfunction "1_1") (pintype "passive"))
      (node (ref "C23") (pin "1") (pinfunction "1_1") (pintype "passive"))
      (node (ref "FB4") (pin "2") (pinfunction "P$2_2") (pintype "passive"))
    )
    (net (code "56") (name "Net-(FB7-P$1)") (class "Default")
      (node (ref "FB7") (pin "1") (pinfunction "P$1_1") (pintype "passive"))
      (node (ref "IC3") (pin "19") (pinfunction "SPK_RN_19") (pintype "output"))
    )
    (net (code "57") (name "Net-(FB8-P$1)") (class "Default")
      (node (ref "FB8") (pin "1") (pinfunction "P$1_1") (pintype "passive"))
      (node (ref "IC3") (pin "22") (pinfunction "SPK_RP_22") (pintype "output"))
    )
    (net (code "58") (name "Net-(FB9-P$1)") (class "Default")
      (node (ref "FB9") (pin "1") (pinfunction "P$1_1") (pintype "passive"))
      (node (ref "IC3") (pin "25") (pinfunction "SPK_LP_25") (pintype "output"))
    )
    (net (code "59") (name "Net-(FB10-P$1)") (class "Default")
      (node (ref "FB10") (pin "1") (pinfunction "P$1_1") (pintype "passive"))
      (node (ref "IC3") (pin "23") (pinfunction "SPK_LN_23") (pintype "output"))
    )
    (net (code "60") (name "Net-(IC3-HP_L)") (class "Default")
      (node (ref "C4") (pin "+") (pinfunction "+_+") (pintype "passive"))
      (node (ref "IC3") (pin "31") (pinfunction "HP_L_31") (pintype "output"))
    )
    (net (code "61") (name "Net-(IC3-HP_R)") (class "Default")
      (node (ref "C6") (pin "+") (pinfunction "+_+") (pintype "passive"))
      (node (ref "IC3") (pin "29") (pinfunction "HP_R_29") (pintype "output"))
    )
    (net (code "62") (name "Net-(LED1-CKO)") (class "Default")
      (node (ref "LED1") (pin "5") (pinfunction "CKO_5") (pintype "output"))
      (node (ref "LED2") (pin "2") (pinfunction "CKI_2") (pintype "input"))
    )
    (net (code "63") (name "Net-(LED1-DO)") (class "Default")
      (node (ref "LED1") (pin "6") (pinfunction "DO_6") (pintype "output"))
      (node (ref "LED2") (pin "1") (pinfunction "DI_1") (pintype "input"))
    )
    (net (code "64") (name "Net-(LED2-CKO)") (class "Default")
      (node (ref "LED2") (pin "5") (pinfunction "CKO_5") (pintype "output"))
      (node (ref "LED3") (pin "2") (pinfunction "CKI_2") (pintype "input"))
    )
    (net (code "65") (name "Net-(LED2-DO)") (class "Default")
      (node (ref "LED2") (pin "6") (pinfunction "DO_6") (pintype "output"))
      (node (ref "LED3") (pin "1") (pinfunction "DI_1") (pintype "input"))
    )
    (net (code "66") (name "PWM0") (class "Default")
      (node (ref "D1") (pin "C") (pinfunction "C_C") (pintype "passive"))
      (node (ref "R7") (pin "2") (pinfunction "2_2") (pintype "passive"))
      (node (ref "RPI1") (pin "32") (pinfunction "GPIO12_32") (pintype "bidirectional"))
      (node (ref "RPI1") (pin "S32") (pinfunction "GPIO12_S32") (pintype "bidirectional"))
    )
    (net (code "67") (name "RIGHT") (class "Default")
      (node (ref "C26") (pin "1") (pinfunction "1_1") (pintype "passive"))
      (node (ref "C6") (pin "-") (pinfunction "-_-") (pintype "passive"))
      (node (ref "R6") (pin "2") (pinfunction "2_2") (pintype "passive"))
      (node (ref "X2") (pin "3") (pinfunction "P$2_3") (pintype "bidirectional"))
      (node (ref "X2") (pin "5") (pinfunction "P$3_5") (pintype "bidirectional"))
    )
    (net (code "68") (name "RIGHT_N") (class "Default")
      (node (ref "C28") (pin "1") (pinfunction "1_1") (pintype "passive"))
      (node (ref "FB7") (pin "2") (pinfunction "P$2_2") (pintype "passive"))
      (node (ref "X5") (pin "2") (pinfunction "2_2") (pintype "passive"))
    )
    (net (code "69") (name "RIGHT_P") (class "Default")
      (node (ref "C29") (pin "1") (pinfunction "1_1") (pintype "passive"))
      (node (ref "FB8") (pin "2") (pinfunction "P$2_2") (pintype "passive"))
      (node (ref "X5") (pin "1") (pinfunction "1_1") (pintype "passive"))
    )
    (net (code "70") (name "RINPUT1") (class "Default")
      (node (ref "C24") (pin "2") (pinfunction "2_2") (pintype "passive"))
      (node (ref "IC3") (pin "5") (pinfunction "RINPUT1_5") (pintype "input"))
    )
    (net (code "71") (name "RXD") (class "Default")
      (node (ref "RPI1") (pin "10") (pinfunction "RXD_10") (pintype "bidirectional"))
      (node (ref "RPI1") (pin "S10") (pinfunction "RXD_S10") (pintype "bidirectional"))
    )
    (net (code "72") (name "SCL") (class "Default")
      (node (ref "CONN3") (pin "4") (pinfunction "SCL_4") (pintype "passive"))
      (node (ref "IC3") (pin "17") (pinfunction "SCL_17") (pintype "input"))
      (node (ref "RPI1") (pin "5") (pinfunction "SCL_5") (pintype "bidirectional"))
      (node (ref "RPI1") (pin "S5") (pinfunction "SCL_S5") (pintype "bidirectional"))
    )
    (net (code "73") (name "SCLK") (class "Default")
      (node (ref "RPI1") (pin "23") (pinfunction "SPI_SCLK_23") (pintype "bidirectional"))
      (node (ref "RPI1") (pin "S23") (pinfunction "SPI_SCLK_S23") (pintype "bidirectional"))
    )
    (net (code "75") (name "SDA") (class "Default")
      (node (ref "CONN3") (pin "3") (pinfunction "SDA_3") (pintype "passive"))
      (node (ref "IC3") (pin "18") (pinfunction "SDA_18") (pintype "bidirectional"))
      (node (ref "RPI1") (pin "3") (pinfunction "SDA_3") (pintype "bidirectional"))
      (node (ref "RPI1") (pin "S3") (pinfunction "SDA_S3") (pintype "bidirectional"))
    )
    (net (code "77") (name "TXD") (class "Default")
      (node (ref "RPI1") (pin "8") (pinfunction "TXD_8") (pintype "bidirectional"))
      (node (ref "RPI1") (pin "S8") (pinfunction "TXD_S8") (pintype "bidirectional"))
    )
    (net (code "79") (name "VCC") (class "Default")
      (node (ref "C34") (pin "1") (pinfunction "1_1") (pintype "passive"))
      (node (ref "NEOPIX") (pin "2") (pinfunction "2_2") (pintype "passive"))
      (node (ref "SJ1") (pin "2") (pinfunction "2_2") (pintype "passive"))
    )
    (net (code "80") (name "VMID") (class "Default")
      (node (ref "C1") (pin "1") (pinfunction "1_1") (pintype "passive"))
      (node (ref "C7") (pin "1") (pinfunction "1_1") (pintype "passive"))
      (node (ref "IC3") (pin "27") (pinfunction "VMID_27") (pintype "input"))
    )
    (net (code "81") (name "unconnected-(IC3-LINPUT2-Pad3)") (class "Default")
      (node (ref "IC3") (pin "3") (pinfunction "LINPUT2_3") (pintype "input"))
    )
    (net (code "82") (name "unconnected-(IC3-LINPUT3-Pad2)") (class "Default")
      (node (ref "IC3") (pin "2") (pinfunction "LINPUT3_2") (pintype "input"))
    )
    (net (code "83") (name "unconnected-(IC3-OUT3-Pad30)") (class "Default")
      (node (ref "IC3") (pin "30") (pinfunction "OUT3_30") (pintype "output"))
    )
    (net (code "84") (name "unconnected-(IC3-RINPUT2-Pad6)") (class "Default")
      (node (ref "IC3") (pin "6") (pinfunction "RINPUT2_6") (pintype "input"))
    )
    (net (code "85") (name "unconnected-(IC3-RINPUT3-Pad7)") (class "Default")
      (node (ref "IC3") (pin "7") (pinfunction "RINPUT3_7") (pintype "input"))
    )
    (net (code "86") (name "unconnected-(LED3-CKO-Pad5)") (class "Default")
      (node (ref "LED3") (pin "5") (pinfunction "CKO_5") (pintype "output"))
    )
    (net (code "87") (name "unconnected-(LED3-DO-Pad6)") (class "Default")
      (node (ref "LED3") (pin "6") (pinfunction "DO_6") (pintype "output"))
    )
    (net (code "88") (name "unconnected-(U3-P4-Pad4)") (class "Default")
      (node (ref "U3") (pin "4") (pinfunction "P4_4") (pintype "bidirectional"))
    )
  )
)
